# adapter_rfm95w_nrf242.net
KiCad netlist of a schematic drawn in EasyEDA Pro
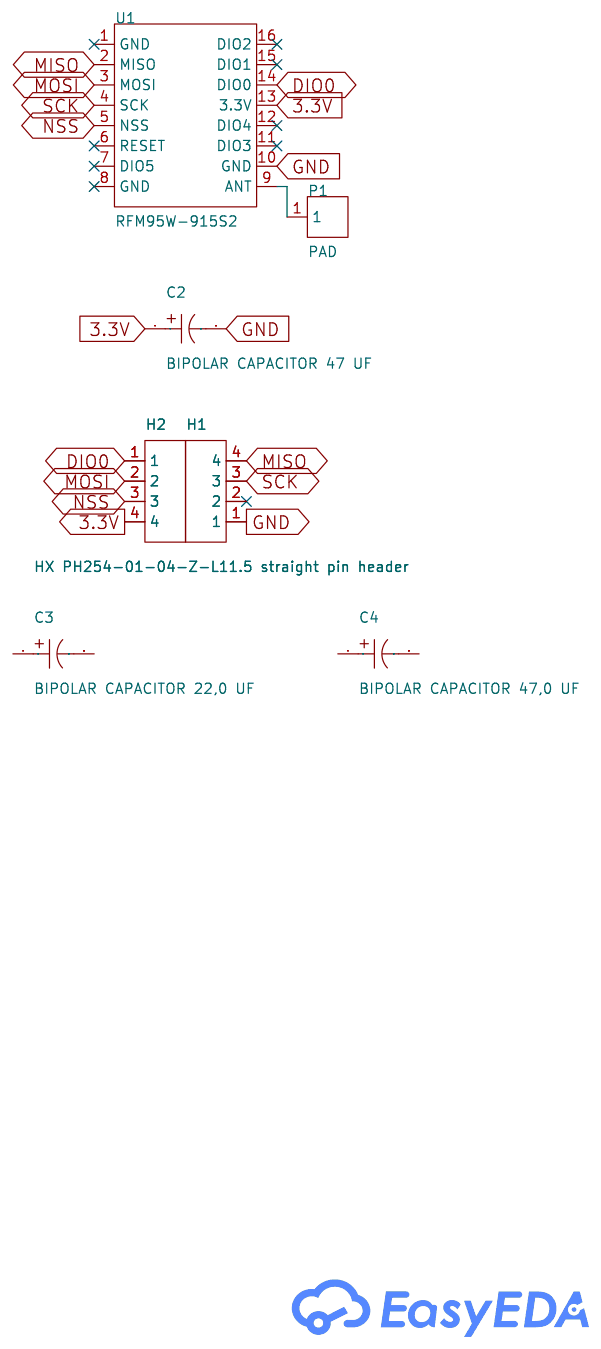
[diagram p0: schematic sheet]

(export (version "E")
  (design (tool "Eeschema 10.0.6"))
  (components
    (comp (ref "C2")
      (value "BIPOLAR CAPACITOR 47 UF")
      (footprint "easyedapro:CAP-TH_BD10.0-P5.00-D0.6-FD")
      (fields (field (name "Manufacturer") "Visaton"))
      (libsource (lib "easyedapro") (part "BIPOLAR CAPACITOR 22,0 UF"))
    )
    (comp (ref "C3")
      (value "BIPOLAR CAPACITOR 22,0 UF")
      (footprint "easyedapro:CAP-TH_BD10.0-P5.00-D0.6-FD")
      (fields (field (name "Manufacturer") "Visaton"))
      (libsource (lib "easyedapro") (part "BIPOLAR CAPACITOR 22,0 UF"))
    )
    (comp (ref "C4")
      (value "BIPOLAR CAPACITOR 47,0 UF")
      (footprint "easyedapro:CAP-TH_BD13.0-P5.00-D0.6-FD")
      (fields (field (name "Manufacturer") "Visaton"))
      (libsource (lib "easyedapro") (part "BIPOLAR CAPACITOR 47,0 UF"))
    )
    (comp (ref "H1")
      (value "HX PH254-01-04-Z-L11.5 straight pin header")
      (footprint "easyedapro:HDR-TH_4P-HX-PH254-01-04-Z-L11.5")
      (fields (field (name "Manufacturer") "hanxia(韩下)"))
      (libsource (lib "easyedapro") (part "HX PH254-01-04-Z-L11.5 STRAIGHT PIN HEADER"))
    )
    (comp (ref "H2")
      (value "HX PH254-01-04-Z-L11.5 straight pin header")
      (footprint "easyedapro:HDR-TH_4P-HX-PH254-01-04-Z-L11.5")
      (fields (field (name "Manufacturer") "hanxia(韩下)"))
      (libsource (lib "easyedapro") (part "HX PH254-01-04-Z-L11.5 STRAIGHT PIN HEADER"))
    )
    (comp (ref "P1")
      (value "PAD")
      (footprint "easyedapro:SMD_BD4.0-L4.0-W4.0-D1.0")
      (libsource (lib "easyedapro") (part "PAD"))
    )
    (comp (ref "U1")
      (value "RFM95W-915S2")
      (footprint "easyedapro:WIRELM-SMD_16P-L16.0-W16.0-P2.00_LORA-CC68-915MHZ-TCXO")
      (fields (field (name "Manufacturer") "RF Solutions"))
      (libsource (lib "easyedapro") (part "RFM95W-915S2"))
    )
  )
  (nets
    (net (code "1") (name "3.3V") (class "Default")
      (node (ref "C2") (pin "1") (pinfunction "1_1") (pintype "input"))
      (node (ref "H2") (pin "4") (pinfunction "4_4") (pintype "unspecified"))
      (node (ref "U1") (pin "13") (pinfunction "3.3V_13") (pintype "unspecified"))
    )
    (net (code "2") (name "DIO0") (class "Default")
      (node (ref "H2") (pin "1") (pinfunction "1_1") (pintype "unspecified"))
      (node (ref "U1") (pin "14") (pinfunction "DIO0_14") (pintype "unspecified"))
    )
    (net (code "3") (name "GND") (class "Default")
      (node (ref "C2") (pin "2") (pinfunction "2_2") (pintype "input"))
      (node (ref "H1") (pin "1") (pinfunction "1_1") (pintype "unspecified"))
      (node (ref "U1") (pin "10") (pinfunction "GND_10") (pintype "unspecified"))
    )
    (net (code "4") (name "MISO") (class "Default")
      (node (ref "H1") (pin "4") (pinfunction "4_4") (pintype "unspecified"))
      (node (ref "U1") (pin "2") (pinfunction "MISO_2") (pintype "unspecified"))
    )
    (net (code "5") (name "MOSI") (class "Default")
      (node (ref "H2") (pin "2") (pinfunction "2_2") (pintype "unspecified"))
      (node (ref "U1") (pin "3") (pinfunction "MOSI_3") (pintype "unspecified"))
    )
    (net (code "6") (name "NSS") (class "Default")
      (node (ref "H2") (pin "3") (pinfunction "3_3") (pintype "unspecified"))
      (node (ref "U1") (pin "5") (pinfunction "NSS_5") (pintype "unspecified"))
    )
    (net (code "7") (name "Net-(U1-ANT)") (class "Default")
      (node (ref "P1") (pin "1") (pinfunction "1_1") (pintype "unspecified"))
      (node (ref "U1") (pin "9") (pinfunction "ANT_9") (pintype "unspecified"))
    )
    (net (code "8") (name "SCK") (class "Default")
      (node (ref "H1") (pin "3") (pinfunction "3_3") (pintype "unspecified"))
      (node (ref "U1") (pin "4") (pinfunction "SCK_4") (pintype "unspecified"))
    )
    (net (code "9") (name "unconnected-(C3-Pad1)") (class "Default")
      (node (ref "C3") (pin "1") (pinfunction "1_1") (pintype "input"))
    )
    (net (code "10") (name "unconnected-(C3-Pad2)") (class "Default")
      (node (ref "C3") (pin "2") (pinfunction "2_2") (pintype "input"))
    )
    (net (code "11") (name "unconnected-(C4-Pad1)") (class "Default")
      (node (ref "C4") (pin "1") (pinfunction "1_1") (pintype "input"))
    )
    (net (code "12") (name "unconnected-(C4-Pad2)") (class "Default")
      (node (ref "C4") (pin "2") (pinfunction "2_2") (pintype "input"))
    )
    (net (code "13") (name "unconnected-(H1-Pad2)") (class "Default")
      (node (ref "H1") (pin "2") (pinfunction "2_2") (pintype "unspecified+no_connect"))
    )
    (net (code "14") (name "unconnected-(U1-DIO1-Pad15)") (class "Default")
      (node (ref "U1") (pin "15") (pinfunction "DIO1_15") (pintype "unspecified+no_connect"))
    )
    (net (code "15") (name "unconnected-(U1-DIO2-Pad16)") (class "Default")
      (node (ref "U1") (pin "16") (pinfunction "DIO2_16") (pintype "unspecified+no_connect"))
    )
    (net (code "16") (name "unconnected-(U1-DIO3-Pad11)") (class "Default")
      (node (ref "U1") (pin "11") (pinfunction "DIO3_11") (pintype "unspecified+no_connect"))
    )
    (net (code "17") (name "unconnected-(U1-DIO4-Pad12)") (class "Default")
      (node (ref "U1") (pin "12") (pinfunction "DIO4_12") (pintype "unspecified+no_connect"))
    )
    (net (code "18") (name "unconnected-(U1-DIO5-Pad7)") (class "Default")
      (node (ref "U1") (pin "7") (pinfunction "DIO5_7") (pintype "unspecified+no_connect"))
    )
    (net (code "19") (name "unconnected-(U1-GND-Pad1)") (class "Default")
      (node (ref "U1") (pin "1") (pinfunction "GND_1") (pintype "unspecified+no_connect"))
    )
    (net (code "20") (name "unconnected-(U1-GND-Pad8)") (class "Default")
      (node (ref "U1") (pin "8") (pinfunction "GND_8") (pintype "unspecified+no_connect"))
    )
    (net (code "21") (name "unconnected-(U1-RESET-Pad6)") (class "Default")
      (node (ref "U1") (pin "6") (pinfunction "RESET_6") (pintype "unspecified+no_connect"))
    )
  )
)
